# MankenMotor.net
KiCad netlist of a schematic drawn in EAGLE
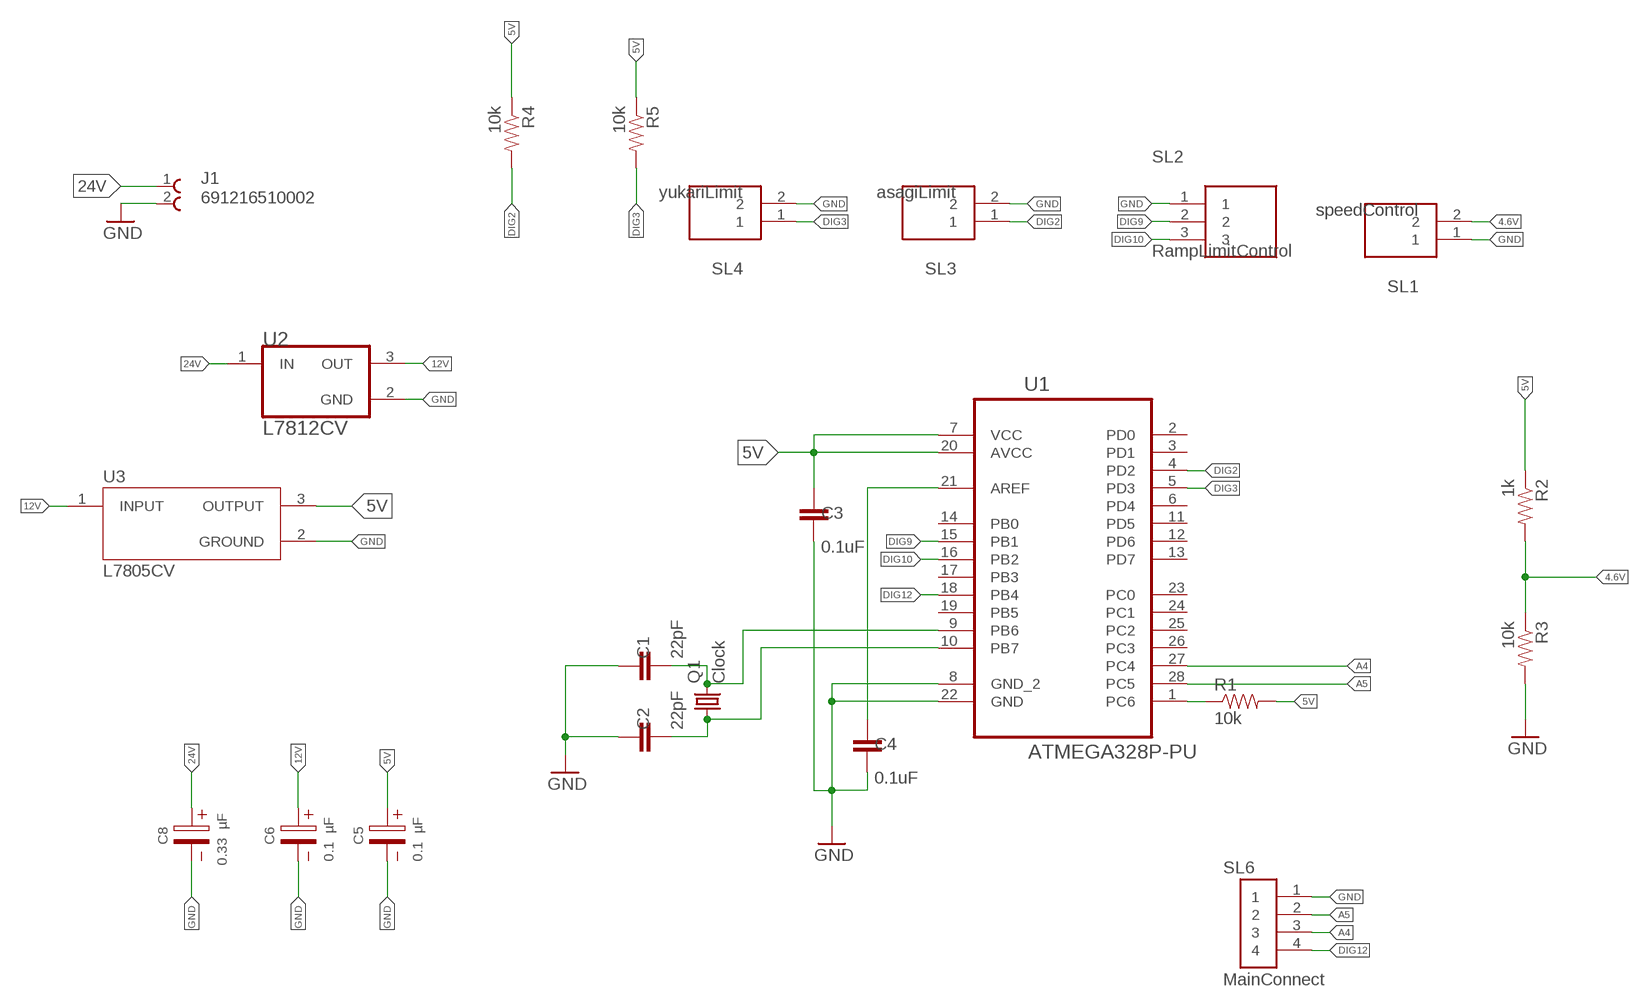
[diagram p0: schematic, sheet 1]

(export (version "E")
  (design (tool "Eeschema 10.0.6"))
  (components
    (comp (ref "C1")
      (value "22pF")
      (footprint "eagle-import:CAP-PTH-2.54")
      (libsource (lib "eagle-import") (part "22PF-PTH-2.54MM-200V-5%"))
    )
    (comp (ref "C2")
      (value "22pF")
      (footprint "eagle-import:CAP-PTH-2.54")
      (libsource (lib "eagle-import") (part "22PF-PTH-2.54MM-200V-5%"))
    )
    (comp (ref "C3")
      (value "0.1uF")
      (footprint "eagle-import:CAP-PTH-SMALL-KIT")
      (libsource (lib "eagle-import") (part "0.1UF-KIT-EZ-50V-20%"))
    )
    (comp (ref "C4")
      (value "0.1uF")
      (footprint "eagle-import:CAP-PTH-SMALL-KIT")
      (libsource (lib "eagle-import") (part "0.1UF-KIT-EZ-50V-20%"))
    )
    (comp (ref "C5")
      (value "0.1 µF")
      (footprint "eagle-import:WCAP-ATG5_5X11(DXL)")
      (libsource (lib "eagle-import") (part "WCAP-ATG5_5X11_860020772001"))
    )
    (comp (ref "C6")
      (value "0.1 µF")
      (footprint "eagle-import:WCAP-ATG5_5X11(DXL)")
      (libsource (lib "eagle-import") (part "WCAP-ATG5_5X11_860020772001"))
    )
    (comp (ref "C8")
      (value "0.33 µF")
      (footprint "eagle-import:WCAP-ATG5_5X11(DXL)")
      (libsource (lib "eagle-import") (part "WCAP-ATG5_5X11_860020772003"))
    )
    (comp (ref "J1")
      (value "691216510002")
      (footprint "eagle-import:691216510002")
      (fields (field (name "MF") "Wurth Electronics"))
      (libsource (lib "eagle-import") (part "691216510002"))
    )
    (comp (ref "Q1")
      (value "Clock")
      (footprint "eagle-import:HC49_S")
      (libsource (lib "eagle-import") (part "CRYSTALHC49S"))
    )
    (comp (ref "R1")
      (value "10k")
      (footprint "eagle-import:AXIAL-0.3")
      (libsource (lib "eagle-import") (part "10KOHM-HORIZ-1/4W-5%"))
    )
    (comp (ref "R2")
      (value "1k")
      (footprint "eagle-import:AXIAL-0.3")
      (libsource (lib "eagle-import") (part "1KOHM-HORIZ-1/4W-5%"))
    )
    (comp (ref "R3")
      (value "10k")
      (footprint "eagle-import:AXIAL-0.3")
      (libsource (lib "eagle-import") (part "10KOHM-HORIZ-1/4W-5%"))
    )
    (comp (ref "R4")
      (value "10k")
      (footprint "eagle-import:AXIAL-0.3")
      (libsource (lib "eagle-import") (part "10KOHM-HORIZ-1/4W-5%"))
    )
    (comp (ref "R5")
      (value "10k")
      (footprint "eagle-import:AXIAL-0.3")
      (libsource (lib "eagle-import") (part "10KOHM-HORIZ-1/4W-5%"))
    )
    (comp (ref "SL1")
      (value "speedControl")
      (footprint "eagle-import:JST_B2B-XH-A(LF)(SN)")
      (fields
        (field (name "DIGI-KEY_PART_NUMBER") "455-2247-ND")
        (field (name "MF") "JST Sales")
        (field (name "MP") "B2B-XH-A(LF)(SN)")
      )
      (libsource (lib "eagle-import") (part "B2B-XH-A(LF)(SN)"))
    )
    (comp (ref "SL2")
      (value "RampLimitControl")
      (footprint "eagle-import:SHDR3W64P0X250_1X3_990X575X700")
      (fields (field (name "ARROW_PART_NUMBER") "B3B-XH-A(LF)(SN)"))
      (libsource (lib "eagle-import") (part "B3B-XH-A_LF__SN_"))
    )
    (comp (ref "SL3")
      (value "asagiLimit")
      (footprint "eagle-import:JST_B2B-XH-A(LF)(SN)")
      (fields
        (field (name "DIGI-KEY_PART_NUMBER") "455-2247-ND")
        (field (name "MF") "JST Sales")
        (field (name "MP") "B2B-XH-A(LF)(SN)")
      )
      (libsource (lib "eagle-import") (part "B2B-XH-A(LF)(SN)"))
    )
    (comp (ref "SL4")
      (value "yukariLimit")
      (footprint "eagle-import:JST_B2B-XH-A(LF)(SN)")
      (fields
        (field (name "DIGI-KEY_PART_NUMBER") "455-2247-ND")
        (field (name "MF") "JST Sales")
        (field (name "MP") "B2B-XH-A(LF)(SN)")
      )
      (libsource (lib "eagle-import") (part "B2B-XH-A(LF)(SN)"))
    )
    (comp (ref "SL6")
      (value "MainConnect")
      (footprint "eagle-import:JST_B4B-XH-A(LF)(SN)")
      (fields
        (field (name "DIGI-KEY_PART_NUMBER") "455-2249-ND")
        (field (name "MF") "JST Sales")
        (field (name "MP") "B4B-XH-A(LF)(SN)")
      )
      (libsource (lib "eagle-import") (part "B4B-XH-A(LF)(SN)"))
    )
    (comp (ref "U1")
      (value "ATMEGA328P-PU")
      (footprint "eagle-import:DIP254P762X457-28")
      (libsource (lib "eagle-import") (part "ATMEGA328P-PU"))
    )
    (comp (ref "U2")
      (value "L7812CV")
      (footprint "eagle-import:TO-220-3")
      (fields (field (name "DIGI-KEY_PART_NUMBER") "497-12406-ND") (field (name "MF") "STMicroelectronics"))
      (libsource (lib "eagle-import") (part "L7812CV"))
    )
    (comp (ref "U3")
      (value "L7805CV")
      (footprint "eagle-import:TO255P1040X460X1968-3")
      (fields (field (name "DIGI-KEY_PART_NUMBER") "497-12404-ND") (field (name "MF") "STMicroelectronics"))
      (libsource (lib "eagle-import") (part "L7805CV"))
    )
  )
  (nets
    (net (code "1") (name "4.6V") (class "Default")
      (node (ref "R2") (pin "P$2") (pinfunction "2_P$2") (pintype "passive"))
      (node (ref "R3") (pin "P$1") (pinfunction "1_P$1") (pintype "passive"))
      (node (ref "SL1") (pin "2") (pinfunction "2_2") (pintype "passive"))
    )
    (net (code "2") (name "5V") (class "Default")
      (node (ref "C3") (pin "1") (pinfunction "1_1") (pintype "passive"))
      (node (ref "C5") (pin "1") (pinfunction "+_1") (pintype "passive"))
      (node (ref "R1") (pin "P$2") (pinfunction "2_P$2") (pintype "passive"))
      (node (ref "R2") (pin "P$1") (pinfunction "1_P$1") (pintype "passive"))
      (node (ref "R4") (pin "P$1") (pinfunction "1_P$1") (pintype "passive"))
      (node (ref "R5") (pin "P$1") (pinfunction "1_P$1") (pintype "passive"))
      (node (ref "U1") (pin "20") (pinfunction "AVCC_20") (pintype "power_in"))
      (node (ref "U1") (pin "7") (pinfunction "VCC_7") (pintype "power_in"))
      (node (ref "U3") (pin "3") (pinfunction "OUTPUT_3") (pintype "output"))
    )
    (net (code "3") (name "12V") (class "Default")
      (node (ref "C6") (pin "1") (pinfunction "+_1") (pintype "passive"))
      (node (ref "U2") (pin "3") (pinfunction "OUT_3") (pintype "output"))
      (node (ref "U3") (pin "1") (pinfunction "INPUT_1") (pintype "input"))
    )
    (net (code "4") (name "24V") (class "Default")
      (node (ref "C8") (pin "1") (pinfunction "+_1") (pintype "passive"))
      (node (ref "J1") (pin "1") (pinfunction "1_1") (pintype "passive"))
      (node (ref "U2") (pin "1") (pinfunction "IN_1") (pintype "input"))
    )
    (net (code "5") (name "A4") (class "Default")
      (node (ref "SL6") (pin "3") (pinfunction "3_3") (pintype "passive"))
      (node (ref "U1") (pin "27") (pinfunction "PC4_27") (pintype "bidirectional"))
    )
    (net (code "6") (name "A5") (class "Default")
      (node (ref "SL6") (pin "2") (pinfunction "2_2") (pintype "passive"))
      (node (ref "U1") (pin "28") (pinfunction "PC5_28") (pintype "bidirectional"))
    )
    (net (code "7") (name "DIG2") (class "Default")
      (node (ref "R4") (pin "P$2") (pinfunction "2_P$2") (pintype "passive"))
      (node (ref "SL3") (pin "1") (pinfunction "1_1") (pintype "passive"))
      (node (ref "U1") (pin "4") (pinfunction "PD2_4") (pintype "bidirectional"))
    )
    (net (code "8") (name "DIG3") (class "Default")
      (node (ref "R5") (pin "P$2") (pinfunction "2_P$2") (pintype "passive"))
      (node (ref "SL4") (pin "1") (pinfunction "1_1") (pintype "passive"))
      (node (ref "U1") (pin "5") (pinfunction "PD3_5") (pintype "bidirectional"))
    )
    (net (code "9") (name "DIG9") (class "Default")
      (node (ref "SL2") (pin "2") (pinfunction "2_2") (pintype "bidirectional"))
      (node (ref "U1") (pin "15") (pinfunction "PB1_15") (pintype "bidirectional"))
    )
    (net (code "10") (name "DIG10") (class "Default")
      (node (ref "SL2") (pin "3") (pinfunction "3_3") (pintype "bidirectional"))
      (node (ref "U1") (pin "16") (pinfunction "PB2_16") (pintype "bidirectional"))
    )
    (net (code "11") (name "DIG12") (class "Default")
      (node (ref "SL6") (pin "4") (pinfunction "4_4") (pintype "passive"))
      (node (ref "U1") (pin "18") (pinfunction "PB4_18") (pintype "bidirectional"))
    )
    (net (code "12") (name "GND") (class "Default")
      (node (ref "C1") (pin "1") (pinfunction "1_1") (pintype "passive"))
      (node (ref "C2") (pin "1") (pinfunction "1_1") (pintype "passive"))
      (node (ref "C3") (pin "2") (pinfunction "2_2") (pintype "passive"))
      (node (ref "C4") (pin "2") (pinfunction "2_2") (pintype "passive"))
      (node (ref "C5") (pin "2") (pinfunction "-_2") (pintype "passive"))
      (node (ref "C6") (pin "2") (pinfunction "-_2") (pintype "passive"))
      (node (ref "C8") (pin "2") (pinfunction "-_2") (pintype "passive"))
      (node (ref "J1") (pin "2") (pinfunction "2_2") (pintype "passive"))
      (node (ref "R3") (pin "P$2") (pinfunction "2_P$2") (pintype "passive"))
      (node (ref "SL1") (pin "1") (pinfunction "1_1") (pintype "passive"))
      (node (ref "SL2") (pin "1") (pinfunction "1_1") (pintype "bidirectional"))
      (node (ref "SL3") (pin "2") (pinfunction "2_2") (pintype "passive"))
      (node (ref "SL4") (pin "2") (pinfunction "2_2") (pintype "passive"))
      (node (ref "SL6") (pin "1") (pinfunction "1_1") (pintype "passive"))
      (node (ref "U1") (pin "22") (pinfunction "GND_22") (pintype "passive"))
      (node (ref "U1") (pin "8") (pinfunction "GND_2_8") (pintype "passive"))
      (node (ref "U2") (pin "2") (pinfunction "GND_2") (pintype "power_in"))
      (node (ref "U3") (pin "2") (pinfunction "GROUND_2") (pintype "power_in"))
    )
    (net (code "13") (name "Net-(R1-1)") (class "Default")
      (node (ref "R1") (pin "P$1") (pinfunction "1_P$1") (pintype "passive"))
      (node (ref "U1") (pin "1") (pinfunction "PC6_1") (pintype "bidirectional"))
    )
    (net (code "14") (name "Net-(U1-AREF)") (class "Default")
      (node (ref "C4") (pin "1") (pinfunction "1_1") (pintype "passive"))
      (node (ref "U1") (pin "21") (pinfunction "AREF_21") (pintype "input"))
    )
    (net (code "15") (name "Net-(U1-PB6)") (class "Default")
      (node (ref "C1") (pin "2") (pinfunction "2_2") (pintype "passive"))
      (node (ref "Q1") (pin "2") (pinfunction "2_2") (pintype "passive"))
      (node (ref "U1") (pin "9") (pinfunction "PB6_9") (pintype "bidirectional"))
    )
    (net (code "16") (name "Net-(U1-PB7)") (class "Default")
      (node (ref "C2") (pin "2") (pinfunction "2_2") (pintype "passive"))
      (node (ref "Q1") (pin "1") (pinfunction "1_1") (pintype "passive"))
      (node (ref "U1") (pin "10") (pinfunction "PB7_10") (pintype "bidirectional"))
    )
    (net (code "17") (name "unconnected-(U1-PB0-Pad14)") (class "Default")
      (node (ref "U1") (pin "14") (pinfunction "PB0_14") (pintype "bidirectional"))
    )
    (net (code "18") (name "unconnected-(U1-PB3-Pad17)") (class "Default")
      (node (ref "U1") (pin "17") (pinfunction "PB3_17") (pintype "bidirectional"))
    )
    (net (code "19") (name "unconnected-(U1-PB5-Pad19)") (class "Default")
      (node (ref "U1") (pin "19") (pinfunction "PB5_19") (pintype "bidirectional"))
    )
    (net (code "20") (name "unconnected-(U1-PC0-Pad23)") (class "Default")
      (node (ref "U1") (pin "23") (pinfunction "PC0_23") (pintype "bidirectional"))
    )
    (net (code "21") (name "unconnected-(U1-PC1-Pad24)") (class "Default")
      (node (ref "U1") (pin "24") (pinfunction "PC1_24") (pintype "bidirectional"))
    )
    (net (code "22") (name "unconnected-(U1-PC2-Pad25)") (class "Default")
      (node (ref "U1") (pin "25") (pinfunction "PC2_25") (pintype "bidirectional"))
    )
    (net (code "23") (name "unconnected-(U1-PC3-Pad26)") (class "Default")
      (node (ref "U1") (pin "26") (pinfunction "PC3_26") (pintype "bidirectional"))
    )
    (net (code "24") (name "unconnected-(U1-PD0-Pad2)") (class "Default")
      (node (ref "U1") (pin "2") (pinfunction "PD0_2") (pintype "bidirectional"))
    )
    (net (code "25") (name "unconnected-(U1-PD1-Pad3)") (class "Default")
      (node (ref "U1") (pin "3") (pinfunction "PD1_3") (pintype "bidirectional"))
    )
    (net (code "26") (name "unconnected-(U1-PD4-Pad6)") (class "Default")
      (node (ref "U1") (pin "6") (pinfunction "PD4_6") (pintype "bidirectional"))
    )
    (net (code "27") (name "unconnected-(U1-PD5-Pad11)") (class "Default")
      (node (ref "U1") (pin "11") (pinfunction "PD5_11") (pintype "bidirectional"))
    )
    (net (code "28") (name "unconnected-(U1-PD6-Pad12)") (class "Default")
      (node (ref "U1") (pin "12") (pinfunction "PD6_12") (pintype "bidirectional"))
    )
    (net (code "29") (name "unconnected-(U1-PD7-Pad13)") (class "Default")
      (node (ref "U1") (pin "13") (pinfunction "PD7_13") (pintype "bidirectional"))
    )
  )
)
